# double-tube.net
KiCad netlist of a schematic drawn in EAGLE
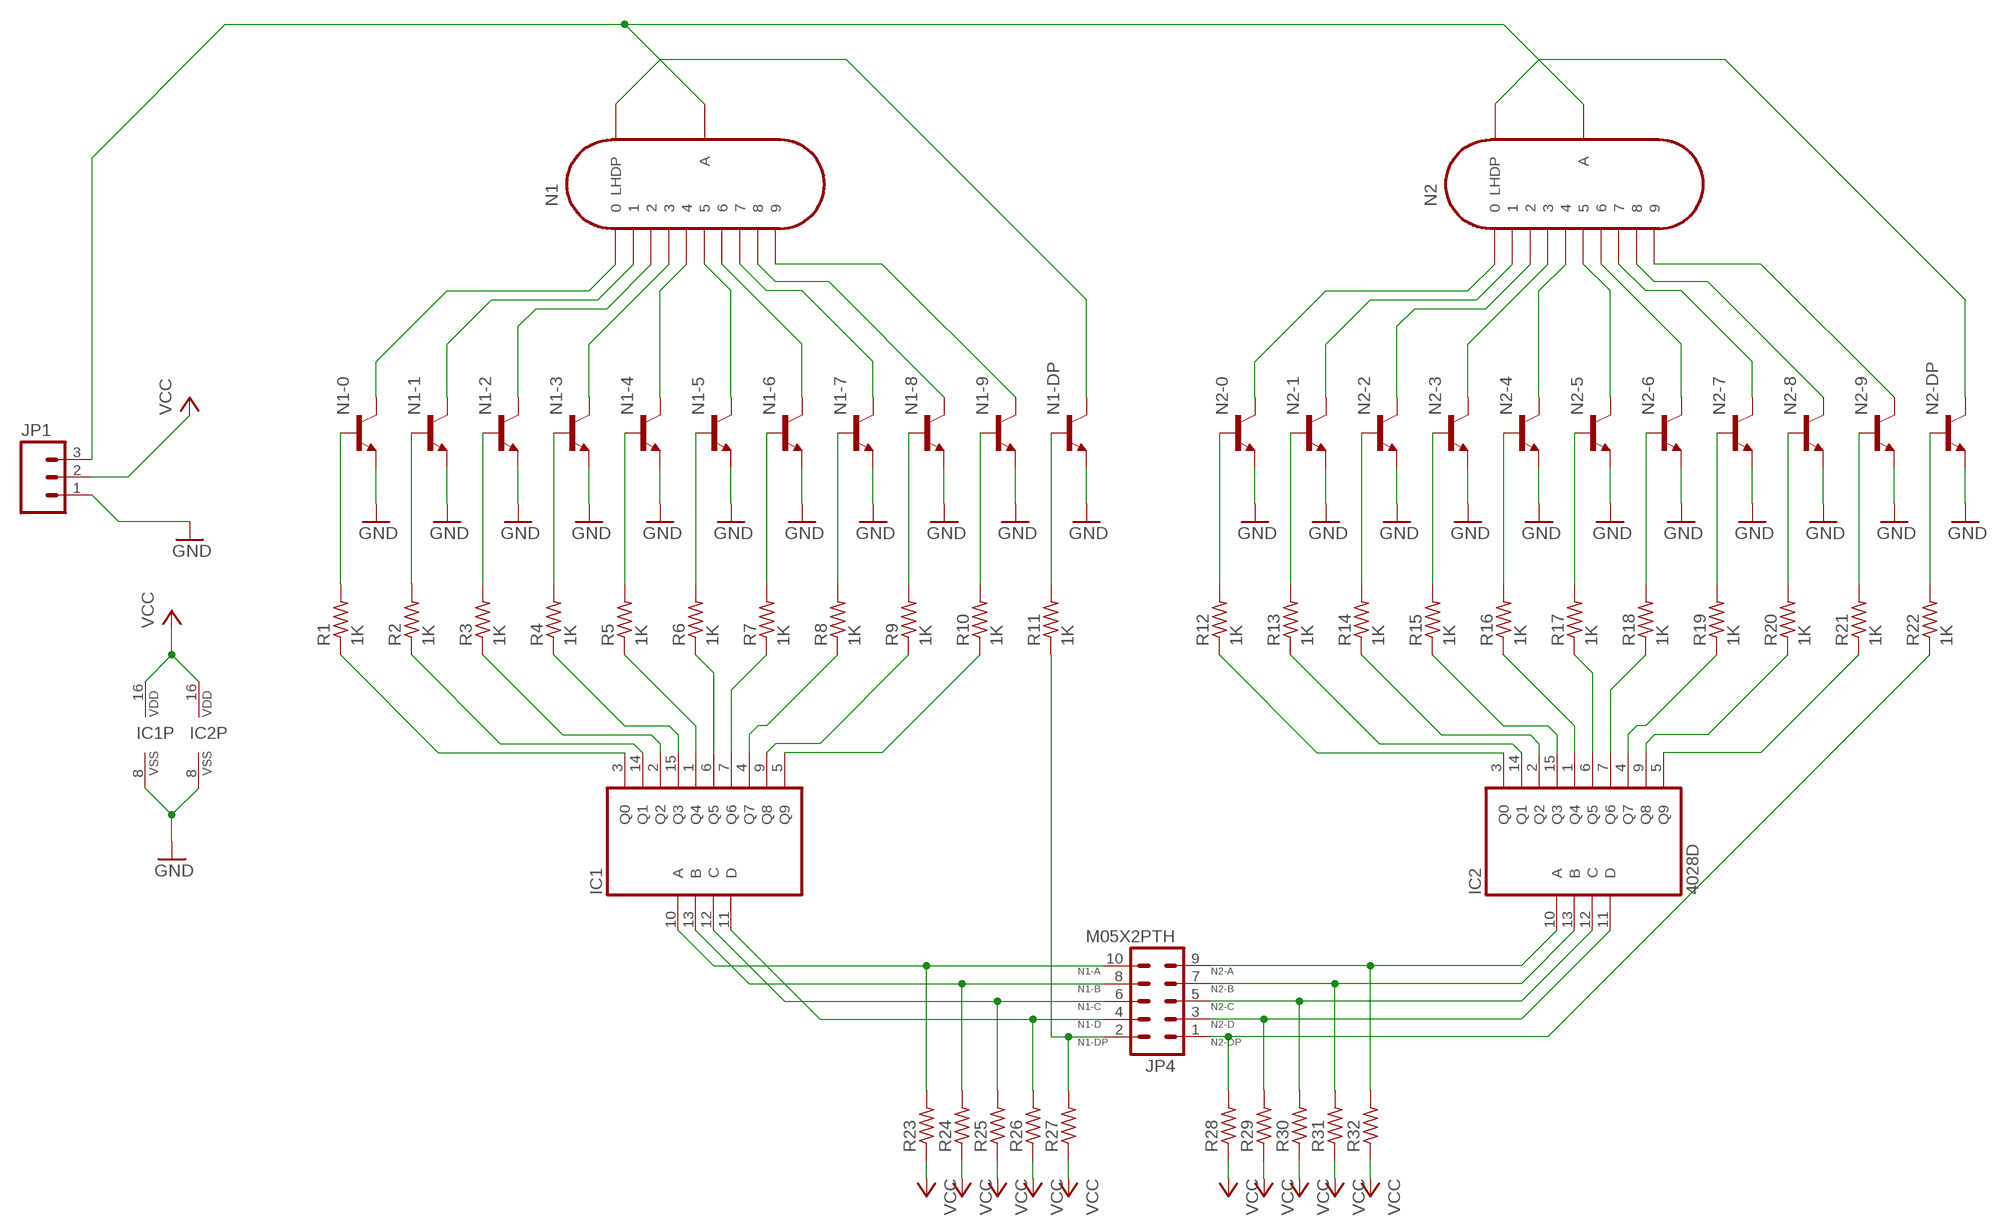
[diagram p0: schematic, sheet 1]

(export (version "E")
  (design (tool "Eeschema 10.0.6"))
  (components
    (comp (ref "IC1")
      (value "4028D")
      (footprint "eagle-import:SO16")
      (libsource (lib "eagle-import") (part "4028D"))
    )
    (comp (ref "IC2")
      (value "4028D")
      (footprint "eagle-import:SO16")
      (libsource (lib "eagle-import") (part "4028D"))
    )
    (comp (ref "JP1")
      (value "M03PTH")
      (footprint "eagle-import:1X03")
      (libsource (lib "eagle-import") (part "M03PTH"))
    )
    (comp (ref "JP4")
      (value "M05X2PTH")
      (footprint "eagle-import:AVR_ICSP")
      (libsource (lib "eagle-import") (part "M05X2PTH"))
    )
    (comp (ref "N1")
      (value "IN-12B")
      (footprint "eagle-import:IN-12")
      (libsource (lib "eagle-import") (part "IN-12B"))
    )
    (comp (ref "N1-0")
      (value "NPN_SMD")
      (footprint "eagle-import:SOT-23")
      (libsource (lib "eagle-import") (part "NPN_SMD"))
    )
    (comp (ref "N1-1")
      (value "NPN_SMD")
      (footprint "eagle-import:SOT-23")
      (libsource (lib "eagle-import") (part "NPN_SMD"))
    )
    (comp (ref "N1-2")
      (value "NPN_SMD")
      (footprint "eagle-import:SOT-23")
      (libsource (lib "eagle-import") (part "NPN_SMD"))
    )
    (comp (ref "N1-3")
      (value "NPN_SMD")
      (footprint "eagle-import:SOT-23")
      (libsource (lib "eagle-import") (part "NPN_SMD"))
    )
    (comp (ref "N1-4")
      (value "NPN_SMD")
      (footprint "eagle-import:SOT-23")
      (libsource (lib "eagle-import") (part "NPN_SMD"))
    )
    (comp (ref "N1-5")
      (value "NPN_SMD")
      (footprint "eagle-import:SOT-23")
      (libsource (lib "eagle-import") (part "NPN_SMD"))
    )
    (comp (ref "N1-6")
      (value "NPN_SMD")
      (footprint "eagle-import:SOT-23")
      (libsource (lib "eagle-import") (part "NPN_SMD"))
    )
    (comp (ref "N1-7")
      (value "NPN_SMD")
      (footprint "eagle-import:SOT-23")
      (libsource (lib "eagle-import") (part "NPN_SMD"))
    )
    (comp (ref "N1-8")
      (value "NPN_SMD")
      (footprint "eagle-import:SOT-23")
      (libsource (lib "eagle-import") (part "NPN_SMD"))
    )
    (comp (ref "N1-9")
      (value "NPN_SMD")
      (footprint "eagle-import:SOT-23")
      (libsource (lib "eagle-import") (part "NPN_SMD"))
    )
    (comp (ref "N1-DP")
      (value "NPN_SMD")
      (footprint "eagle-import:SOT-23")
      (libsource (lib "eagle-import") (part "NPN_SMD"))
    )
    (comp (ref "N2")
      (value "IN-12B")
      (footprint "eagle-import:IN-12")
      (libsource (lib "eagle-import") (part "IN-12B"))
    )
    (comp (ref "N2-0")
      (value "NPN_SMD")
      (footprint "eagle-import:SOT-23")
      (libsource (lib "eagle-import") (part "NPN_SMD"))
    )
    (comp (ref "N2-1")
      (value "NPN_SMD")
      (footprint "eagle-import:SOT-23")
      (libsource (lib "eagle-import") (part "NPN_SMD"))
    )
    (comp (ref "N2-2")
      (value "NPN_SMD")
      (footprint "eagle-import:SOT-23")
      (libsource (lib "eagle-import") (part "NPN_SMD"))
    )
    (comp (ref "N2-3")
      (value "NPN_SMD")
      (footprint "eagle-import:SOT-23")
      (libsource (lib "eagle-import") (part "NPN_SMD"))
    )
    (comp (ref "N2-4")
      (value "NPN_SMD")
      (footprint "eagle-import:SOT-23")
      (libsource (lib "eagle-import") (part "NPN_SMD"))
    )
    (comp (ref "N2-5")
      (value "NPN_SMD")
      (footprint "eagle-import:SOT-23")
      (libsource (lib "eagle-import") (part "NPN_SMD"))
    )
    (comp (ref "N2-6")
      (value "NPN_SMD")
      (footprint "eagle-import:SOT-23")
      (libsource (lib "eagle-import") (part "NPN_SMD"))
    )
    (comp (ref "N2-7")
      (value "NPN_SMD")
      (footprint "eagle-import:SOT-23")
      (libsource (lib "eagle-import") (part "NPN_SMD"))
    )
    (comp (ref "N2-8")
      (value "NPN_SMD")
      (footprint "eagle-import:SOT-23")
      (libsource (lib "eagle-import") (part "NPN_SMD"))
    )
    (comp (ref "N2-9")
      (value "NPN_SMD")
      (footprint "eagle-import:SOT-23")
      (libsource (lib "eagle-import") (part "NPN_SMD"))
    )
    (comp (ref "N2-DP")
      (value "NPN_SMD")
      (footprint "eagle-import:SOT-23")
      (libsource (lib "eagle-import") (part "NPN_SMD"))
    )
    (comp (ref "R1")
      (value "1K")
      (footprint "eagle-import:R0603")
      (libsource (lib "eagle-import") (part "RESISTORR0603"))
    )
    (comp (ref "R2")
      (value "1K")
      (footprint "eagle-import:R0603")
      (libsource (lib "eagle-import") (part "RESISTORR0603"))
    )
    (comp (ref "R3")
      (value "1K")
      (footprint "eagle-import:R0603")
      (libsource (lib "eagle-import") (part "RESISTORR0603"))
    )
    (comp (ref "R4")
      (value "1K")
      (footprint "eagle-import:R0603")
      (libsource (lib "eagle-import") (part "RESISTORR0603"))
    )
    (comp (ref "R5")
      (value "1K")
      (footprint "eagle-import:R0603")
      (libsource (lib "eagle-import") (part "RESISTORR0603"))
    )
    (comp (ref "R6")
      (value "1K")
      (footprint "eagle-import:R0603")
      (libsource (lib "eagle-import") (part "RESISTORR0603"))
    )
    (comp (ref "R7")
      (value "1K")
      (footprint "eagle-import:R0603")
      (libsource (lib "eagle-import") (part "RESISTORR0603"))
    )
    (comp (ref "R8")
      (value "1K")
      (footprint "eagle-import:R0603")
      (libsource (lib "eagle-import") (part "RESISTORR0603"))
    )
    (comp (ref "R9")
      (value "1K")
      (footprint "eagle-import:R0603")
      (libsource (lib "eagle-import") (part "RESISTORR0603"))
    )
    (comp (ref "R10")
      (value "1K")
      (footprint "eagle-import:R0603")
      (libsource (lib "eagle-import") (part "RESISTORR0603"))
    )
    (comp (ref "R11")
      (value "1K")
      (footprint "eagle-import:R0603")
      (libsource (lib "eagle-import") (part "RESISTORR0603"))
    )
    (comp (ref "R12")
      (value "1K")
      (footprint "eagle-import:R0603")
      (libsource (lib "eagle-import") (part "RESISTORR0603"))
    )
    (comp (ref "R13")
      (value "1K")
      (footprint "eagle-import:R0603")
      (libsource (lib "eagle-import") (part "RESISTORR0603"))
    )
    (comp (ref "R14")
      (value "1K")
      (footprint "eagle-import:R0603")
      (libsource (lib "eagle-import") (part "RESISTORR0603"))
    )
    (comp (ref "R15")
      (value "1K")
      (footprint "eagle-import:R0603")
      (libsource (lib "eagle-import") (part "RESISTORR0603"))
    )
    (comp (ref "R16")
      (value "1K")
      (footprint "eagle-import:R0603")
      (libsource (lib "eagle-import") (part "RESISTORR0603"))
    )
    (comp (ref "R17")
      (value "1K")
      (footprint "eagle-import:R0603")
      (libsource (lib "eagle-import") (part "RESISTORR0603"))
    )
    (comp (ref "R18")
      (value "1K")
      (footprint "eagle-import:R0603")
      (libsource (lib "eagle-import") (part "RESISTORR0603"))
    )
    (comp (ref "R19")
      (value "1K")
      (footprint "eagle-import:R0603")
      (libsource (lib "eagle-import") (part "RESISTORR0603"))
    )
    (comp (ref "R20")
      (value "1K")
      (footprint "eagle-import:R0603")
      (libsource (lib "eagle-import") (part "RESISTORR0603"))
    )
    (comp (ref "R21")
      (value "1K")
      (footprint "eagle-import:R0603")
      (libsource (lib "eagle-import") (part "RESISTORR0603"))
    )
    (comp (ref "R22")
      (value "1K")
      (footprint "eagle-import:R0603")
      (libsource (lib "eagle-import") (part "RESISTORR0603"))
    )
    (comp (ref "R23")
      (value "RESISTORR0603")
      (footprint "eagle-import:R0603")
      (libsource (lib "eagle-import") (part "RESISTORR0603"))
    )
    (comp (ref "R24")
      (value "RESISTORR0603")
      (footprint "eagle-import:R0603")
      (libsource (lib "eagle-import") (part "RESISTORR0603"))
    )
    (comp (ref "R25")
      (value "RESISTORR0603")
      (footprint "eagle-import:R0603")
      (libsource (lib "eagle-import") (part "RESISTORR0603"))
    )
    (comp (ref "R26")
      (value "RESISTORR0603")
      (footprint "eagle-import:R0603")
      (libsource (lib "eagle-import") (part "RESISTORR0603"))
    )
    (comp (ref "R27")
      (value "RESISTORR0603")
      (footprint "eagle-import:R0603")
      (libsource (lib "eagle-import") (part "RESISTORR0603"))
    )
    (comp (ref "R28")
      (value "RESISTORR0603")
      (footprint "eagle-import:R0603")
      (libsource (lib "eagle-import") (part "RESISTORR0603"))
    )
    (comp (ref "R29")
      (value "RESISTORR0603")
      (footprint "eagle-import:R0603")
      (libsource (lib "eagle-import") (part "RESISTORR0603"))
    )
    (comp (ref "R30")
      (value "RESISTORR0603")
      (footprint "eagle-import:R0603")
      (libsource (lib "eagle-import") (part "RESISTORR0603"))
    )
    (comp (ref "R31")
      (value "RESISTORR0603")
      (footprint "eagle-import:R0603")
      (libsource (lib "eagle-import") (part "RESISTORR0603"))
    )
    (comp (ref "R32")
      (value "RESISTORR0603")
      (footprint "eagle-import:R0603")
      (libsource (lib "eagle-import") (part "RESISTORR0603"))
    )
  )
  (nets
    (net (code "1") (name "/N1-A") (class "Default")
      (node (ref "IC1") (pin "10") (pinfunction "A_10") (pintype "input"))
      (node (ref "JP4") (pin "10") (pinfunction "10_10") (pintype "passive"))
      (node (ref "R23") (pin "2") (pinfunction "2_2") (pintype "passive"))
    )
    (net (code "2") (name "/N1-B") (class "Default")
      (node (ref "IC1") (pin "13") (pinfunction "B_13") (pintype "input"))
      (node (ref "JP4") (pin "8") (pinfunction "8_8") (pintype "passive"))
      (node (ref "R24") (pin "2") (pinfunction "2_2") (pintype "passive"))
    )
    (net (code "3") (name "/N1-C") (class "Default")
      (node (ref "IC1") (pin "12") (pinfunction "C_12") (pintype "input"))
      (node (ref "JP4") (pin "6") (pinfunction "6_6") (pintype "passive"))
      (node (ref "R25") (pin "2") (pinfunction "2_2") (pintype "passive"))
    )
    (net (code "4") (name "/N1-D") (class "Default")
      (node (ref "IC1") (pin "11") (pinfunction "D_11") (pintype "input"))
      (node (ref "JP4") (pin "4") (pinfunction "4_4") (pintype "passive"))
      (node (ref "R26") (pin "2") (pinfunction "2_2") (pintype "passive"))
    )
    (net (code "5") (name "/N1-DP") (class "Default")
      (node (ref "JP4") (pin "2") (pinfunction "2_2") (pintype "passive"))
      (node (ref "R11") (pin "1") (pinfunction "1_1") (pintype "passive"))
      (node (ref "R27") (pin "2") (pinfunction "2_2") (pintype "passive"))
    )
    (net (code "6") (name "/N2-A") (class "Default")
      (node (ref "IC2") (pin "10") (pinfunction "A_10") (pintype "input"))
      (node (ref "JP4") (pin "9") (pinfunction "9_9") (pintype "passive"))
      (node (ref "R32") (pin "2") (pinfunction "2_2") (pintype "passive"))
    )
    (net (code "7") (name "/N2-B") (class "Default")
      (node (ref "IC2") (pin "13") (pinfunction "B_13") (pintype "input"))
      (node (ref "JP4") (pin "7") (pinfunction "7_7") (pintype "passive"))
      (node (ref "R31") (pin "2") (pinfunction "2_2") (pintype "passive"))
    )
    (net (code "8") (name "/N2-C") (class "Default")
      (node (ref "IC2") (pin "12") (pinfunction "C_12") (pintype "input"))
      (node (ref "JP4") (pin "5") (pinfunction "5_5") (pintype "passive"))
      (node (ref "R30") (pin "2") (pinfunction "2_2") (pintype "passive"))
    )
    (net (code "9") (name "/N2-D") (class "Default")
      (node (ref "IC2") (pin "11") (pinfunction "D_11") (pintype "input"))
      (node (ref "JP4") (pin "3") (pinfunction "3_3") (pintype "passive"))
      (node (ref "R29") (pin "2") (pinfunction "2_2") (pintype "passive"))
    )
    (net (code "10") (name "/N2-DP") (class "Default")
      (node (ref "JP4") (pin "1") (pinfunction "1_1") (pintype "passive"))
      (node (ref "R22") (pin "1") (pinfunction "1_1") (pintype "passive"))
      (node (ref "R28") (pin "2") (pinfunction "2_2") (pintype "passive"))
    )
    (net (code "11") (name "GND") (class "Default")
      (node (ref "IC1") (pin "8") (pinfunction "VSS_8") (pintype "power_in"))
      (node (ref "IC2") (pin "8") (pinfunction "VSS_8") (pintype "power_in"))
      (node (ref "JP1") (pin "1") (pinfunction "1_1") (pintype "passive"))
      (node (ref "N1-0") (pin "2") (pinfunction "E_2") (pintype "passive"))
      (node (ref "N1-1") (pin "2") (pinfunction "E_2") (pintype "passive"))
      (node (ref "N1-2") (pin "2") (pinfunction "E_2") (pintype "passive"))
      (node (ref "N1-3") (pin "2") (pinfunction "E_2") (pintype "passive"))
      (node (ref "N1-4") (pin "2") (pinfunction "E_2") (pintype "passive"))
      (node (ref "N1-5") (pin "2") (pinfunction "E_2") (pintype "passive"))
      (node (ref "N1-6") (pin "2") (pinfunction "E_2") (pintype "passive"))
      (node (ref "N1-7") (pin "2") (pinfunction "E_2") (pintype "passive"))
      (node (ref "N1-8") (pin "2") (pinfunction "E_2") (pintype "passive"))
      (node (ref "N1-9") (pin "2") (pinfunction "E_2") (pintype "passive"))
      (node (ref "N1-DP") (pin "2") (pinfunction "E_2") (pintype "passive"))
      (node (ref "N2-0") (pin "2") (pinfunction "E_2") (pintype "passive"))
      (node (ref "N2-1") (pin "2") (pinfunction "E_2") (pintype "passive"))
      (node (ref "N2-2") (pin "2") (pinfunction "E_2") (pintype "passive"))
      (node (ref "N2-3") (pin "2") (pinfunction "E_2") (pintype "passive"))
      (node (ref "N2-4") (pin "2") (pinfunction "E_2") (pintype "passive"))
      (node (ref "N2-5") (pin "2") (pinfunction "E_2") (pintype "passive"))
      (node (ref "N2-6") (pin "2") (pinfunction "E_2") (pintype "passive"))
      (node (ref "N2-7") (pin "2") (pinfunction "E_2") (pintype "passive"))
      (node (ref "N2-8") (pin "2") (pinfunction "E_2") (pintype "passive"))
      (node (ref "N2-9") (pin "2") (pinfunction "E_2") (pintype "passive"))
      (node (ref "N2-DP") (pin "2") (pinfunction "E_2") (pintype "passive"))
    )
    (net (code "12") (name "Net-(IC1A-Q0)") (class "Default")
      (node (ref "IC1") (pin "3") (pinfunction "Q0_3") (pintype "output"))
      (node (ref "R1") (pin "1") (pinfunction "1_1") (pintype "passive"))
    )
    (net (code "13") (name "Net-(IC1A-Q1)") (class "Default")
      (node (ref "IC1") (pin "14") (pinfunction "Q1_14") (pintype "output"))
      (node (ref "R2") (pin "1") (pinfunction "1_1") (pintype "passive"))
    )
    (net (code "14") (name "Net-(IC1A-Q2)") (class "Default")
      (node (ref "IC1") (pin "2") (pinfunction "Q2_2") (pintype "output"))
      (node (ref "R3") (pin "1") (pinfunction "1_1") (pintype "passive"))
    )
    (net (code "15") (name "Net-(IC1A-Q3)") (class "Default")
      (node (ref "IC1") (pin "15") (pinfunction "Q3_15") (pintype "output"))
      (node (ref "R4") (pin "1") (pinfunction "1_1") (pintype "passive"))
    )
    (net (code "16") (name "Net-(IC1A-Q4)") (class "Default")
      (node (ref "IC1") (pin "1") (pinfunction "Q4_1") (pintype "output"))
      (node (ref "R5") (pin "1") (pinfunction "1_1") (pintype "passive"))
    )
    (net (code "17") (name "Net-(IC1A-Q5)") (class "Default")
      (node (ref "IC1") (pin "6") (pinfunction "Q5_6") (pintype "output"))
      (node (ref "R6") (pin "1") (pinfunction "1_1") (pintype "passive"))
    )
    (net (code "18") (name "Net-(IC1A-Q6)") (class "Default")
      (node (ref "IC1") (pin "7") (pinfunction "Q6_7") (pintype "output"))
      (node (ref "R7") (pin "1") (pinfunction "1_1") (pintype "passive"))
    )
    (net (code "19") (name "Net-(IC1A-Q7)") (class "Default")
      (node (ref "IC1") (pin "4") (pinfunction "Q7_4") (pintype "output"))
      (node (ref "R8") (pin "1") (pinfunction "1_1") (pintype "passive"))
    )
    (net (code "20") (name "Net-(IC1A-Q8)") (class "Default")
      (node (ref "IC1") (pin "9") (pinfunction "Q8_9") (pintype "output"))
      (node (ref "R9") (pin "1") (pinfunction "1_1") (pintype "passive"))
    )
    (net (code "21") (name "Net-(IC1A-Q9)") (class "Default")
      (node (ref "IC1") (pin "5") (pinfunction "Q9_5") (pintype "output"))
      (node (ref "R10") (pin "1") (pinfunction "1_1") (pintype "passive"))
    )
    (net (code "22") (name "Net-(IC2A-Q0)") (class "Default")
      (node (ref "IC2") (pin "3") (pinfunction "Q0_3") (pintype "output"))
      (node (ref "R12") (pin "1") (pinfunction "1_1") (pintype "passive"))
    )
    (net (code "23") (name "Net-(IC2A-Q1)") (class "Default")
      (node (ref "IC2") (pin "14") (pinfunction "Q1_14") (pintype "output"))
      (node (ref "R13") (pin "1") (pinfunction "1_1") (pintype "passive"))
    )
    (net (code "24") (name "Net-(IC2A-Q2)") (class "Default")
      (node (ref "IC2") (pin "2") (pinfunction "Q2_2") (pintype "output"))
      (node (ref "R14") (pin "1") (pinfunction "1_1") (pintype "passive"))
    )
    (net (code "25") (name "Net-(IC2A-Q3)") (class "Default")
      (node (ref "IC2") (pin "15") (pinfunction "Q3_15") (pintype "output"))
      (node (ref "R15") (pin "1") (pinfunction "1_1") (pintype "passive"))
    )
    (net (code "26") (name "Net-(IC2A-Q4)") (class "Default")
      (node (ref "IC2") (pin "1") (pinfunction "Q4_1") (pintype "output"))
      (node (ref "R16") (pin "1") (pinfunction "1_1") (pintype "passive"))
    )
    (net (code "27") (name "Net-(IC2A-Q5)") (class "Default")
      (node (ref "IC2") (pin "6") (pinfunction "Q5_6") (pintype "output"))
      (node (ref "R17") (pin "1") (pinfunction "1_1") (pintype "passive"))
    )
    (net (code "28") (name "Net-(IC2A-Q6)") (class "Default")
      (node (ref "IC2") (pin "7") (pinfunction "Q6_7") (pintype "output"))
      (node (ref "R18") (pin "1") (pinfunction "1_1") (pintype "passive"))
    )
    (net (code "29") (name "Net-(IC2A-Q7)") (class "Default")
      (node (ref "IC2") (pin "4") (pinfunction "Q7_4") (pintype "output"))
      (node (ref "R19") (pin "1") (pinfunction "1_1") (pintype "passive"))
    )
    (net (code "30") (name "Net-(IC2A-Q8)") (class "Default")
      (node (ref "IC2") (pin "9") (pinfunction "Q8_9") (pintype "output"))
      (node (ref "R20") (pin "1") (pinfunction "1_1") (pintype "passive"))
    )
    (net (code "31") (name "Net-(IC2A-Q9)") (class "Default")
      (node (ref "IC2") (pin "5") (pinfunction "Q9_5") (pintype "output"))
      (node (ref "R21") (pin "1") (pinfunction "1_1") (pintype "passive"))
    )
    (net (code "32") (name "Net-(JP1-Pad3)") (class "Default")
      (node (ref "JP1") (pin "3") (pinfunction "3_3") (pintype "passive"))
      (node (ref "N1") (pin "A") (pinfunction "A_A") (pintype "bidirectional"))
      (node (ref "N2") (pin "A") (pinfunction "A_A") (pintype "bidirectional"))
    )
    (net (code "33") (name "Net-(N1-0-B)") (class "Default")
      (node (ref "N1-0") (pin "1") (pinfunction "B_1") (pintype "passive"))
      (node (ref "R1") (pin "2") (pinfunction "2_2") (pintype "passive"))
    )
    (net (code "34") (name "Net-(N1-0-C)") (class "Default")
      (node (ref "N1") (pin "0") (pinfunction "0_0") (pintype "bidirectional"))
      (node (ref "N1-0") (pin "3") (pinfunction "C_3") (pintype "passive"))
    )
    (net (code "35") (name "Net-(N1-1-B)") (class "Default")
      (node (ref "N1-1") (pin "1") (pinfunction "B_1") (pintype "passive"))
      (node (ref "R2") (pin "2") (pinfunction "2_2") (pintype "passive"))
    )
    (net (code "36") (name "Net-(N1-1-C)") (class "Default")
      (node (ref "N1") (pin "1") (pinfunction "1_1") (pintype "bidirectional"))
      (node (ref "N1-1") (pin "3") (pinfunction "C_3") (pintype "passive"))
    )
    (net (code "37") (name "Net-(N1-2-B)") (class "Default")
      (node (ref "N1-2") (pin "1") (pinfunction "B_1") (pintype "passive"))
      (node (ref "R3") (pin "2") (pinfunction "2_2") (pintype "passive"))
    )
    (net (code "38") (name "Net-(N1-2-C)") (class "Default")
      (node (ref "N1") (pin "2") (pinfunction "2_2") (pintype "bidirectional"))
      (node (ref "N1-2") (pin "3") (pinfunction "C_3") (pintype "passive"))
    )
    (net (code "39") (name "Net-(N1-3-B)") (class "Default")
      (node (ref "N1-3") (pin "1") (pinfunction "B_1") (pintype "passive"))
      (node (ref "R4") (pin "2") (pinfunction "2_2") (pintype "passive"))
    )
    (net (code "40") (name "Net-(N1-3-C)") (class "Default")
      (node (ref "N1") (pin "3") (pinfunction "3_3") (pintype "bidirectional"))
      (node (ref "N1-3") (pin "3") (pinfunction "C_3") (pintype "passive"))
    )
    (net (code "41") (name "Net-(N1-4-B)") (class "Default")
      (node (ref "N1-4") (pin "1") (pinfunction "B_1") (pintype "passive"))
      (node (ref "R5") (pin "2") (pinfunction "2_2") (pintype "passive"))
    )
    (net (code "42") (name "Net-(N1-4-C)") (class "Default")
      (node (ref "N1") (pin "4") (pinfunction "4_4") (pintype "bidirectional"))
      (node (ref "N1-4") (pin "3") (pinfunction "C_3") (pintype "passive"))
    )
    (net (code "43") (name "Net-(N1-5-B)") (class "Default")
      (node (ref "N1-5") (pin "1") (pinfunction "B_1") (pintype "passive"))
      (node (ref "R6") (pin "2") (pinfunction "2_2") (pintype "passive"))
    )
    (net (code "44") (name "Net-(N1-5-C)") (class "Default")
      (node (ref "N1") (pin "5") (pinfunction "5_5") (pintype "bidirectional"))
      (node (ref "N1-5") (pin "3") (pinfunction "C_3") (pintype "passive"))
    )
    (net (code "45") (name "Net-(N1-6-B)") (class "Default")
      (node (ref "N1-6") (pin "1") (pinfunction "B_1") (pintype "passive"))
      (node (ref "R7") (pin "2") (pinfunction "2_2") (pintype "passive"))
    )
    (net (code "46") (name "Net-(N1-6-C)") (class "Default")
      (node (ref "N1") (pin "6") (pinfunction "6_6") (pintype "bidirectional"))
      (node (ref "N1-6") (pin "3") (pinfunction "C_3") (pintype "passive"))
    )
    (net (code "47") (name "Net-(N1-7-B)") (class "Default")
      (node (ref "N1-7") (pin "1") (pinfunction "B_1") (pintype "passive"))
      (node (ref "R8") (pin "2") (pinfunction "2_2") (pintype "passive"))
    )
    (net (code "48") (name "Net-(N1-7-C)") (class "Default")
      (node (ref "N1") (pin "7") (pinfunction "7_7") (pintype "bidirectional"))
      (node (ref "N1-7") (pin "3") (pinfunction "C_3") (pintype "passive"))
    )
    (net (code "49") (name "Net-(N1-8-B)") (class "Default")
      (node (ref "N1-8") (pin "1") (pinfunction "B_1") (pintype "passive"))
      (node (ref "R9") (pin "2") (pinfunction "2_2") (pintype "passive"))
    )
    (net (code "50") (name "Net-(N1-8-C)") (class "Default")
      (node (ref "N1") (pin "8") (pinfunction "8_8") (pintype "bidirectional"))
      (node (ref "N1-8") (pin "3") (pinfunction "C_3") (pintype "passive"))
    )
    (net (code "51") (name "Net-(N1-9-B)") (class "Default")
      (node (ref "N1-9") (pin "1") (pinfunction "B_1") (pintype "passive"))
      (node (ref "R10") (pin "2") (pinfunction "2_2") (pintype "passive"))
    )
    (net (code "52") (name "Net-(N1-9-C)") (class "Default")
      (node (ref "N1") (pin "9") (pinfunction "9_9") (pintype "bidirectional"))
      (node (ref "N1-9") (pin "3") (pinfunction "C_3") (pintype "passive"))
    )
    (net (code "53") (name "Net-(N1-DP-B)") (class "Default")
      (node (ref "N1-DP") (pin "1") (pinfunction "B_1") (pintype "passive"))
      (node (ref "R11") (pin "2") (pinfunction "2_2") (pintype "passive"))
    )
    (net (code "54") (name "Net-(N1-DP-C)") (class "Default")
      (node (ref "N1") (pin "LHDP") (pinfunction "LHDP_LHDP") (pintype "bidirectional"))
      (node (ref "N1-DP") (pin "3") (pinfunction "C_3") (pintype "passive"))
    )
    (net (code "55") (name "Net-(N2-0-B)") (class "Default")
      (node (ref "N2-0") (pin "1") (pinfunction "B_1") (pintype "passive"))
      (node (ref "R12") (pin "2") (pinfunction "2_2") (pintype "passive"))
    )
    (net (code "56") (name "Net-(N2-0-C)") (class "Default")
      (node (ref "N2") (pin "0") (pinfunction "0_0") (pintype "bidirectional"))
      (node (ref "N2-0") (pin "3") (pinfunction "C_3") (pintype "passive"))
    )
    (net (code "57") (name "Net-(N2-1-B)") (class "Default")
      (node (ref "N2-1") (pin "1") (pinfunction "B_1") (pintype "passive"))
      (node (ref "R13") (pin "2") (pinfunction "2_2") (pintype "passive"))
    )
    (net (code "58") (name "Net-(N2-1-C)") (class "Default")
      (node (ref "N2") (pin "1") (pinfunction "1_1") (pintype "bidirectional"))
      (node (ref "N2-1") (pin "3") (pinfunction "C_3") (pintype "passive"))
    )
    (net (code "59") (name "Net-(N2-2-B)") (class "Default")
      (node (ref "N2-2") (pin "1") (pinfunction "B_1") (pintype "passive"))
      (node (ref "R14") (pin "2") (pinfunction "2_2") (pintype "passive"))
    )
    (net (code "60") (name "Net-(N2-2-C)") (class "Default")
      (node (ref "N2") (pin "2") (pinfunction "2_2") (pintype "bidirectional"))
      (node (ref "N2-2") (pin "3") (pinfunction "C_3") (pintype "passive"))
    )
    (net (code "61") (name "Net-(N2-3-B)") (class "Default")
      (node (ref "N2-3") (pin "1") (pinfunction "B_1") (pintype "passive"))
      (node (ref "R15") (pin "2") (pinfunction "2_2") (pintype "passive"))
    )
    (net (code "62") (name "Net-(N2-3-C)") (class "Default")
      (node (ref "N2") (pin "3") (pinfunction "3_3") (pintype "bidirectional"))
      (node (ref "N2-3") (pin "3") (pinfunction "C_3") (pintype "passive"))
    )
    (net (code "63") (name "Net-(N2-4-B)") (class "Default")
      (node (ref "N2-4") (pin "1") (pinfunction "B_1") (pintype "passive"))
      (node (ref "R16") (pin "2") (pinfunction "2_2") (pintype "passive"))
    )
    (net (code "64") (name "Net-(N2-4-C)") (class "Default")
      (node (ref "N2") (pin "4") (pinfunction "4_4") (pintype "bidirectional"))
      (node (ref "N2-4") (pin "3") (pinfunction "C_3") (pintype "passive"))
    )
    (net (code "65") (name "Net-(N2-5-B)") (class "Default")
      (node (ref "N2-5") (pin "1") (pinfunction "B_1") (pintype "passive"))
      (node (ref "R17") (pin "2") (pinfunction "2_2") (pintype "passive"))
    )
    (net (code "66") (name "Net-(N2-5-C)") (class "Default")
      (node (ref "N2") (pin "5") (pinfunction "5_5") (pintype "bidirectional"))
      (node (ref "N2-5") (pin "3") (pinfunction "C_3") (pintype "passive"))
    )
    (net (code "67") (name "Net-(N2-6-B)") (class "Default")
      (node (ref "N2-6") (pin "1") (pinfunction "B_1") (pintype "passive"))
      (node (ref "R18") (pin "2") (pinfunction "2_2") (pintype "passive"))
    )
    (net (code "68") (name "Net-(N2-6-C)") (class "Default")
      (node (ref "N2") (pin "6") (pinfunction "6_6") (pintype "bidirectional"))
      (node (ref "N2-6") (pin "3") (pinfunction "C_3") (pintype "passive"))
    )
    (net (code "69") (name "Net-(N2-7-B)") (class "Default")
      (node (ref "N2-7") (pin "1") (pinfunction "B_1") (pintype "passive"))
      (node (ref "R19") (pin "2") (pinfunction "2_2") (pintype "passive"))
    )
    (net (code "70") (name "Net-(N2-7-C)") (class "Default")
      (node (ref "N2") (pin "7") (pinfunction "7_7") (pintype "bidirectional"))
      (node (ref "N2-7") (pin "3") (pinfunction "C_3") (pintype "passive"))
    )
    (net (code "71") (name "Net-(N2-8-B)") (class "Default")
      (node (ref "N2-8") (pin "1") (pinfunction "B_1") (pintype "passive"))
      (node (ref "R20") (pin "2") (pinfunction "2_2") (pintype "passive"))
    )
    (net (code "72") (name "Net-(N2-8-C)") (class "Default")
      (node (ref "N2") (pin "8") (pinfunction "8_8") (pintype "bidirectional"))
      (node (ref "N2-8") (pin "3") (pinfunction "C_3") (pintype "passive"))
    )
    (net (code "73") (name "Net-(N2-9-B)") (class "Default")
      (node (ref "N2-9") (pin "1") (pinfunction "B_1") (pintype "passive"))
      (node (ref "R21") (pin "2") (pinfunction "2_2") (pintype "passive"))
    )
    (net (code "74") (name "Net-(N2-9-C)") (class "Default")
      (node (ref "N2") (pin "9") (pinfunction "9_9") (pintype "bidirectional"))
      (node (ref "N2-9") (pin "3") (pinfunction "C_3") (pintype "passive"))
    )
    (net (code "75") (name "Net-(N2-DP-B)") (class "Default")
      (node (ref "N2-DP") (pin "1") (pinfunction "B_1") (pintype "passive"))
      (node (ref "R22") (pin "2") (pinfunction "2_2") (pintype "passive"))
    )
    (net (code "76") (name "Net-(N2-DP-C)") (class "Default")
      (node (ref "N2") (pin "LHDP") (pinfunction "LHDP_LHDP") (pintype "bidirectional"))
      (node (ref "N2-DP") (pin "3") (pinfunction "C_3") (pintype "passive"))
    )
    (net (code "77") (name "VCC") (class "Default")
      (node (ref "IC1") (pin "16") (pinfunction "VDD_16") (pintype "power_in"))
      (node (ref "IC2") (pin "16") (pinfunction "VDD_16") (pintype "power_in"))
      (node (ref "JP1") (pin "2") (pinfunction "2_2") (pintype "passive"))
      (node (ref "R23") (pin "1") (pinfunction "1_1") (pintype "passive"))
      (node (ref "R24") (pin "1") (pinfunction "1_1") (pintype "passive"))
      (node (ref "R25") (pin "1") (pinfunction "1_1") (pintype "passive"))
      (node (ref "R26") (pin "1") (pinfunction "1_1") (pintype "passive"))
      (node (ref "R27") (pin "1") (pinfunction "1_1") (pintype "passive"))
      (node (ref "R28") (pin "1") (pinfunction "1_1") (pintype "passive"))
      (node (ref "R29") (pin "1") (pinfunction "1_1") (pintype "passive"))
      (node (ref "R30") (pin "1") (pinfunction "1_1") (pintype "passive"))
      (node (ref "R31") (pin "1") (pinfunction "1_1") (pintype "passive"))
      (node (ref "R32") (pin "1") (pinfunction "1_1") (pintype "passive"))
    )
  )
)
